# sc.net
KiCad netlist of a schematic drawn in EAGLE
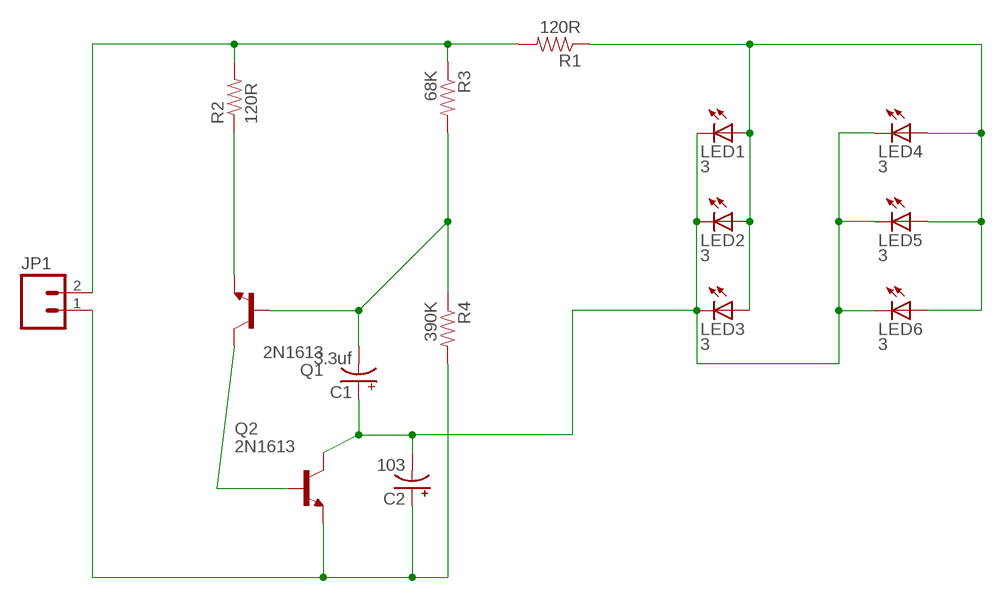
[diagram p0: schematic, sheet 1]

(export (version "E")
  (design (tool "Eeschema 10.0.6"))
  (components
    (comp (ref "C1")
      (value "3.3uf")
      (footprint "eagle-import:CPOL-RADIAL-10UF-25V")
      (libsource (lib "eagle-import") (part "CAP_POLPTH2"))
    )
    (comp (ref "C2")
      (value "103")
      (footprint "eagle-import:CPOL-RADIAL-10UF-25V")
      (libsource (lib "eagle-import") (part "CAP_POLPTH2"))
    )
    (comp (ref "JP1")
      (value "M02JST-PTH-2")
      (footprint "eagle-import:JST-2-PTH")
      (libsource (lib "eagle-import") (part "M02JST-PTH-2"))
    )
    (comp (ref "LED1")
      (value "3")
      (footprint "eagle-import:LED3MM")
      (libsource (lib "eagle-import") (part "LED3MM"))
    )
    (comp (ref "LED2")
      (value "3")
      (footprint "eagle-import:LED3MM")
      (libsource (lib "eagle-import") (part "LED3MM"))
    )
    (comp (ref "LED3")
      (value "3")
      (footprint "eagle-import:LED3MM")
      (libsource (lib "eagle-import") (part "LED3MM"))
    )
    (comp (ref "LED4")
      (value "3")
      (footprint "eagle-import:LED3MM")
      (libsource (lib "eagle-import") (part "LED3MM"))
    )
    (comp (ref "LED5")
      (value "3")
      (footprint "eagle-import:LED3MM")
      (libsource (lib "eagle-import") (part "LED3MM"))
    )
    (comp (ref "LED6")
      (value "3")
      (footprint "eagle-import:LED3MM")
      (libsource (lib "eagle-import") (part "LED3MM"))
    )
    (comp (ref "Q1")
      (value "2N1613")
      (footprint "eagle-import:TO5")
      (libsource (lib "eagle-import") (part "2N1613"))
    )
    (comp (ref "Q2")
      (value "2N1613")
      (footprint "eagle-import:TO5")
      (libsource (lib "eagle-import") (part "2N1613"))
    )
    (comp (ref "R1")
      (value "120R")
      (footprint "eagle-import:AXIAL-0.4")
      (libsource (lib "eagle-import") (part "RESISTORPTH-1/4W"))
    )
    (comp (ref "R2")
      (value "120R")
      (footprint "eagle-import:AXIAL-0.4")
      (libsource (lib "eagle-import") (part "RESISTORPTH-1/4W"))
    )
    (comp (ref "R3")
      (value "68K")
      (footprint "eagle-import:AXIAL-0.4")
      (libsource (lib "eagle-import") (part "RESISTORPTH-1/4W"))
    )
    (comp (ref "R4")
      (value "390K")
      (footprint "eagle-import:AXIAL-0.4")
      (libsource (lib "eagle-import") (part "RESISTORPTH-1/4W"))
    )
  )
  (nets
    (net (code "1") (name "Net-(C1-+)") (class "Default")
      (node (ref "C1") (pin "1") (pinfunction "+_1") (pintype "passive"))
      (node (ref "C2") (pin "2") (pinfunction "-_2") (pintype "passive"))
      (node (ref "LED1") (pin "K") (pinfunction "C_K") (pintype "passive"))
      (node (ref "LED2") (pin "K") (pinfunction "C_K") (pintype "passive"))
      (node (ref "LED3") (pin "K") (pinfunction "C_K") (pintype "passive"))
      (node (ref "LED4") (pin "K") (pinfunction "C_K") (pintype "passive"))
      (node (ref "LED5") (pin "K") (pinfunction "C_K") (pintype "passive"))
      (node (ref "LED6") (pin "K") (pinfunction "C_K") (pintype "passive"))
      (node (ref "Q2") (pin "3") (pinfunction "C_3") (pintype "passive"))
    )
    (net (code "2") (name "Net-(C1--)") (class "Default")
      (node (ref "C1") (pin "2") (pinfunction "-_2") (pintype "passive"))
      (node (ref "Q1") (pin "2") (pinfunction "B_2") (pintype "passive"))
      (node (ref "R3") (pin "P$2") (pinfunction "2_P$2") (pintype "passive"))
      (node (ref "R4") (pin "P$1") (pinfunction "1_P$1") (pintype "passive"))
    )
    (net (code "3") (name "Net-(C2-+)") (class "Default")
      (node (ref "C2") (pin "1") (pinfunction "+_1") (pintype "passive"))
      (node (ref "JP1") (pin "1") (pinfunction "1_1") (pintype "passive"))
      (node (ref "Q2") (pin "1") (pinfunction "E_1") (pintype "passive"))
      (node (ref "R4") (pin "P$2") (pinfunction "2_P$2") (pintype "passive"))
    )
    (net (code "4") (name "Net-(Q1-C)") (class "Default")
      (node (ref "Q1") (pin "3") (pinfunction "C_3") (pintype "passive"))
      (node (ref "Q2") (pin "2") (pinfunction "B_2") (pintype "passive"))
    )
    (net (code "5") (name "Net-(Q1-E)") (class "Default")
      (node (ref "Q1") (pin "1") (pinfunction "E_1") (pintype "passive"))
      (node (ref "R2") (pin "P$1") (pinfunction "1_P$1") (pintype "passive"))
    )
    (net (code "6") (name "Net-(R1-1)") (class "Default")
      (node (ref "LED1") (pin "A") (pinfunction "A_A") (pintype "passive"))
      (node (ref "LED2") (pin "A") (pinfunction "A_A") (pintype "passive"))
      (node (ref "LED3") (pin "A") (pinfunction "A_A") (pintype "passive"))
      (node (ref "LED4") (pin "A") (pinfunction "A_A") (pintype "passive"))
      (node (ref "LED5") (pin "A") (pinfunction "A_A") (pintype "passive"))
      (node (ref "LED6") (pin "A") (pinfunction "A_A") (pintype "passive"))
      (node (ref "R1") (pin "P$1") (pinfunction "1_P$1") (pintype "passive"))
    )
    (net (code "7") (name "Net-(R1-2)") (class "Default")
      (node (ref "JP1") (pin "2") (pinfunction "2_2") (pintype "passive"))
      (node (ref "R1") (pin "P$2") (pinfunction "2_P$2") (pintype "passive"))
      (node (ref "R2") (pin "P$2") (pinfunction "2_P$2") (pintype "passive"))
      (node (ref "R3") (pin "P$1") (pinfunction "1_P$1") (pintype "passive"))
    )
  )
)
